# ESP8266-Programmer_v3.net
KiCad netlist of a schematic drawn in EAGLE
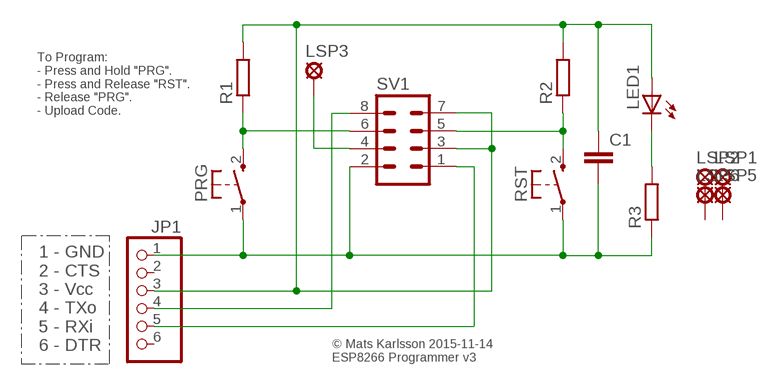
[diagram p0: schematic, sheet 1]

(export (version "E")
  (design (tool "Eeschema 10.0.6"))
  (components
    (comp (ref "C1")
      (value "C-EU025_050-035X075")
      (footprint "eagle-import:C025_050-035X075")
      (libsource (lib "eagle-import") (part "C-EU025_050-035X075"))
    )
    (comp (ref "JP1")
      (value "PINHD-1X6")
      (footprint "eagle-import:1X06")
      (libsource (lib "eagle-import") (part "PINHD-1X6"))
    )
    (comp (ref "LED1")
      (value "TLLG4400")
      (footprint "eagle-import:LED3MM")
      (fields (field (name "MF") "VISHAY SEMICONDUCTOR"))
      (libsource (lib "eagle-import") (part "TLLG4400"))
    )
    (comp (ref "LSP1")
      (value "SE11")
      (footprint "eagle-import:SE11")
      (libsource (lib "eagle-import") (part "SE11"))
    )
    (comp (ref "LSP2")
      (value "SE11")
      (footprint "eagle-import:SE11")
      (libsource (lib "eagle-import") (part "SE11"))
    )
    (comp (ref "LSP3")
      (value "SE11")
      (footprint "eagle-import:SE11")
      (libsource (lib "eagle-import") (part "SE11"))
    )
    (comp (ref "LSP5")
      (value "SE11")
      (footprint "eagle-import:SE11")
      (libsource (lib "eagle-import") (part "SE11"))
    )
    (comp (ref "LSP6")
      (value "SE11")
      (footprint "eagle-import:SE11")
      (libsource (lib "eagle-import") (part "SE11"))
    )
    (comp (ref "PRG")
      (value "KSS-2EG4430")
      (footprint "eagle-import:KSS-2EG4430")
      (libsource (lib "eagle-import") (part "KSS-2EG4430"))
    )
    (comp (ref "R1")
      (value "R-EU_0204/5")
      (footprint "eagle-import:0204_5")
      (libsource (lib "eagle-import") (part "R-EU_0204/5"))
    )
    (comp (ref "R2")
      (value "R-EU_0204/5")
      (footprint "eagle-import:0204_5")
      (libsource (lib "eagle-import") (part "R-EU_0204/5"))
    )
    (comp (ref "R3")
      (value "R-EU_0204/7")
      (footprint "eagle-import:0204_7")
      (libsource (lib "eagle-import") (part "R-EU_0204/7"))
    )
    (comp (ref "RST")
      (value "KSS-2EG4430")
      (footprint "eagle-import:KSS-2EG4430")
      (libsource (lib "eagle-import") (part "KSS-2EG4430"))
    )
    (comp (ref "SV1")
      (value "MA04-2")
      (footprint "eagle-import:MA04-2")
      (libsource (lib "eagle-import") (part "MA04-2"))
    )
  )
  (nets
    (net (code "1") (name "Net-(C1-Pad1)") (class "Default")
      (node (ref "C1") (pin "1") (pinfunction "1_1") (pintype "passive"))
      (node (ref "JP1") (pin "3") (pinfunction "3_3") (pintype "passive"))
      (node (ref "LED1") (pin "A") (pinfunction "A_A") (pintype "passive"))
      (node (ref "R1") (pin "2") (pinfunction "2_2") (pintype "passive"))
      (node (ref "R2") (pin "2") (pinfunction "2_2") (pintype "passive"))
      (node (ref "SV1") (pin "3") (pinfunction "3_3") (pintype "passive"))
      (node (ref "SV1") (pin "7") (pinfunction "7_7") (pintype "passive"))
    )
    (net (code "2") (name "Net-(JP1-Pad4)") (class "Default")
      (node (ref "JP1") (pin "4") (pinfunction "4_4") (pintype "passive"))
      (node (ref "SV1") (pin "8") (pinfunction "8_8") (pintype "passive"))
    )
    (net (code "3") (name "Net-(JP1-Pad5)") (class "Default")
      (node (ref "JP1") (pin "5") (pinfunction "5_5") (pintype "passive"))
      (node (ref "SV1") (pin "1") (pinfunction "1_1") (pintype "passive"))
    )
    (net (code "4") (name "Net-(LED1-C)") (class "Default")
      (node (ref "LED1") (pin "K") (pinfunction "C_K") (pintype "passive"))
      (node (ref "R3") (pin "2") (pinfunction "2_2") (pintype "passive"))
    )
    (net (code "5") (name "Net-(LSP3-PadMP)") (class "Default")
      (node (ref "LSP3") (pin "MP") (pinfunction "MP_MP") (pintype "passive"))
      (node (ref "SV1") (pin "4") (pinfunction "4_4") (pintype "passive"))
    )
    (net (code "6") (name "Net-(PRG-P)") (class "Default")
      (node (ref "C1") (pin "2") (pinfunction "2_2") (pintype "passive"))
      (node (ref "JP1") (pin "1") (pinfunction "1_1") (pintype "passive"))
      (node (ref "PRG") (pin "1") (pinfunction "P_1") (pintype "passive"))
      (node (ref "R3") (pin "1") (pinfunction "1_1") (pintype "passive"))
      (node (ref "RST") (pin "1") (pinfunction "P_1") (pintype "passive"))
      (node (ref "SV1") (pin "2") (pinfunction "2_2") (pintype "passive"))
    )
    (net (code "7") (name "Net-(PRG-S)") (class "Default")
      (node (ref "PRG") (pin "2") (pinfunction "S_2") (pintype "passive"))
      (node (ref "R1") (pin "1") (pinfunction "1_1") (pintype "passive"))
      (node (ref "SV1") (pin "6") (pinfunction "6_6") (pintype "passive"))
    )
    (net (code "8") (name "Net-(RST-S)") (class "Default")
      (node (ref "R2") (pin "1") (pinfunction "1_1") (pintype "passive"))
      (node (ref "RST") (pin "2") (pinfunction "S_2") (pintype "passive"))
      (node (ref "SV1") (pin "5") (pinfunction "5_5") (pintype "passive"))
    )
    (net (code "9") (name "unconnected-(JP1-Pad2)") (class "Default")
      (node (ref "JP1") (pin "2") (pinfunction "2_2") (pintype "passive"))
    )
    (net (code "10") (name "unconnected-(JP1-Pad6)") (class "Default")
      (node (ref "JP1") (pin "6") (pinfunction "6_6") (pintype "passive"))
    )
    (net (code "11") (name "unconnected-(LSP1-PadMP)") (class "Default")
      (node (ref "LSP1") (pin "MP") (pinfunction "MP_MP") (pintype "passive"))
    )
    (net (code "12") (name "unconnected-(LSP2-PadMP)") (class "Default")
      (node (ref "LSP2") (pin "MP") (pinfunction "MP_MP") (pintype "passive"))
    )
    (net (code "13") (name "unconnected-(LSP5-PadMP)") (class "Default")
      (node (ref "LSP5") (pin "MP") (pinfunction "MP_MP") (pintype "passive"))
    )
    (net (code "14") (name "unconnected-(LSP6-PadMP)") (class "Default")
      (node (ref "LSP6") (pin "MP") (pinfunction "MP_MP") (pintype "passive"))
    )
  )
)
